# CANTransceiver.net
KiCad netlist of a schematic drawn in Altium Designer
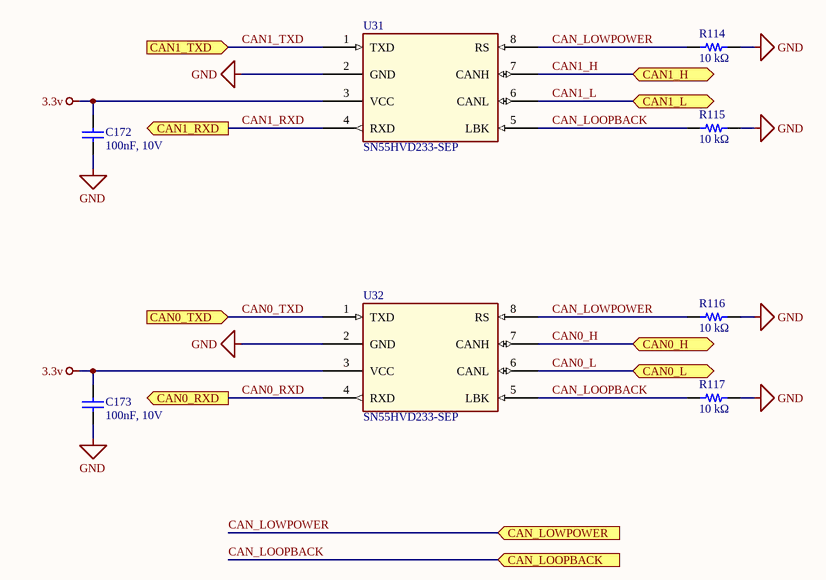
[diagram p0: CANTransceiver.SchDoc]

(export (version "E")
  (design (tool "Eeschema 10.0.6"))
  (components
    (comp (ref "C172")
      (value "100nF, 10V")
      (footprint "WURTH_WCAP-CSGP_0402")
      (description "WCAP-CSGP Multilayer Ceramic Chip Capacitor, General Purpose, size 0402, X7R, 100nF, 10V")
      (fields
        (field (name "MANUFACTURER PART NUMBER") "885012205018")
        (field (name "MANUFACTURER") "Wurth Elektronik")
      )
      (libsource (lib "SpaceVNX") (part "885012205018"))
    )
    (comp (ref "C173")
      (value "100nF, 10V")
      (footprint "WURTH_WCAP-CSGP_0402")
      (description "WCAP-CSGP Multilayer Ceramic Chip Capacitor, General Purpose, size 0402, X7R, 100nF, 10V")
      (fields
        (field (name "MANUFACTURER PART NUMBER") "885012205018")
        (field (name "MANUFACTURER") "Wurth Elektronik")
      )
      (libsource (lib "SpaceVNX") (part "885012205018"))
    )
    (comp (ref "R114")
      (value "10 kΩ")
      (footprint "PANASONIC_ERJ2G_0402")
      (description "General Purpose Thick Film Chip Resistors")
      (fields (field (name "MANUFACTURER") "Panasonic"))
      (libsource (lib "SpaceVNX") (part "ERJ2RKF1002X"))
    )
    (comp (ref "R115")
      (value "10 kΩ")
      (footprint "PANASONIC_ERJ2G_0402")
      (description "General Purpose Thick Film Chip Resistors")
      (fields (field (name "MANUFACTURER") "Panasonic"))
      (libsource (lib "SpaceVNX") (part "ERJ2RKF1002X"))
    )
    (comp (ref "R116")
      (value "10 kΩ")
      (footprint "PANASONIC_ERJ2G_0402")
      (description "General Purpose Thick Film Chip Resistors")
      (fields (field (name "MANUFACTURER") "Panasonic"))
      (libsource (lib "SpaceVNX") (part "ERJ2RKF1002X"))
    )
    (comp (ref "R117")
      (value "10 kΩ")
      (footprint "PANASONIC_ERJ2G_0402")
      (description "General Purpose Thick Film Chip Resistors")
      (fields (field (name "MANUFACTURER") "Panasonic"))
      (libsource (lib "SpaceVNX") (part "ERJ2RKF1002X"))
    )
    (comp (ref "U31")
      (value "SN55HVD233-SEP")
      (footprint "TEXAS_SOIC8D")
      (description "Radiation hardened 3.3V CAN transceiver in space enhanced plastic package with standby mode")
      (libsource (lib "SpaceVNX") (part "SN55HVD233-SEP"))
    )
    (comp (ref "U32")
      (value "SN55HVD233-SEP")
      (footprint "TEXAS_SOIC8D")
      (description "Radiation hardened 3.3V CAN transceiver in space enhanced plastic package with standby mode")
      (libsource (lib "SpaceVNX") (part "SN55HVD233-SEP"))
    )
  )
  (nets
    (net (code "1") (name "/CAN0_H") (class "Default")
      (node (ref "U32") (pin "7") (pinfunction "CANH_7") (pintype "bidirectional"))
    )
    (net (code "2") (name "/CAN0_L") (class "Default")
      (node (ref "U32") (pin "6") (pinfunction "CANL_6") (pintype "bidirectional"))
    )
    (net (code "3") (name "/CAN0_RXD") (class "Default")
      (node (ref "U32") (pin "4") (pinfunction "RXD_4") (pintype "output"))
    )
    (net (code "4") (name "/CAN0_TXD") (class "Default")
      (node (ref "U32") (pin "1") (pinfunction "TXD_1") (pintype "input"))
    )
    (net (code "5") (name "/CAN1_H") (class "Default")
      (node (ref "U31") (pin "7") (pinfunction "CANH_7") (pintype "bidirectional"))
    )
    (net (code "6") (name "/CAN1_L") (class "Default")
      (node (ref "U31") (pin "6") (pinfunction "CANL_6") (pintype "bidirectional"))
    )
    (net (code "7") (name "/CAN1_RXD") (class "Default")
      (node (ref "U31") (pin "4") (pinfunction "RXD_4") (pintype "output"))
    )
    (net (code "8") (name "/CAN1_TXD") (class "Default")
      (node (ref "U31") (pin "1") (pinfunction "TXD_1") (pintype "input"))
    )
    (net (code "9") (name "/CAN_LOOPBACK") (class "Default")
      (node (ref "R115") (pin "1") (pinfunction "1_1") (pintype "passive"))
      (node (ref "R117") (pin "1") (pinfunction "1_1") (pintype "passive"))
      (node (ref "U31") (pin "5") (pinfunction "LBK_5") (pintype "input"))
      (node (ref "U32") (pin "5") (pinfunction "LBK_5") (pintype "input"))
    )
    (net (code "10") (name "/CAN_LOWPOWER") (class "Default")
      (node (ref "R114") (pin "1") (pinfunction "1_1") (pintype "passive"))
      (node (ref "R116") (pin "1") (pinfunction "1_1") (pintype "passive"))
      (node (ref "U31") (pin "8") (pinfunction "RS_8") (pintype "input"))
      (node (ref "U32") (pin "8") (pinfunction "RS_8") (pintype "input"))
    )
    (net (code "11") (name "3.3v") (class "Default")
      (node (ref "C172") (pin "2") (pinfunction "2_2") (pintype "passive"))
      (node (ref "C173") (pin "2") (pinfunction "2_2") (pintype "passive"))
      (node (ref "U31") (pin "3") (pinfunction "VCC_3") (pintype "power_in"))
      (node (ref "U32") (pin "3") (pinfunction "VCC_3") (pintype "power_in"))
    )
    (net (code "12") (name "GND") (class "Default")
      (node (ref "C172") (pin "1") (pinfunction "1_1") (pintype "passive"))
      (node (ref "C173") (pin "1") (pinfunction "1_1") (pintype "passive"))
      (node (ref "R114") (pin "2") (pinfunction "2_2") (pintype "passive"))
      (node (ref "R115") (pin "2") (pinfunction "2_2") (pintype "passive"))
      (node (ref "R116") (pin "2") (pinfunction "2_2") (pintype "passive"))
      (node (ref "R117") (pin "2") (pinfunction "2_2") (pintype "passive"))
      (node (ref "U31") (pin "2") (pinfunction "GND_2") (pintype "passive"))
      (node (ref "U32") (pin "2") (pinfunction "GND_2") (pintype "passive"))
    )
  )
)
